# slush_cap_board_hardctrl_rev_C.net
KiCad netlist of a schematic drawn in EAGLE
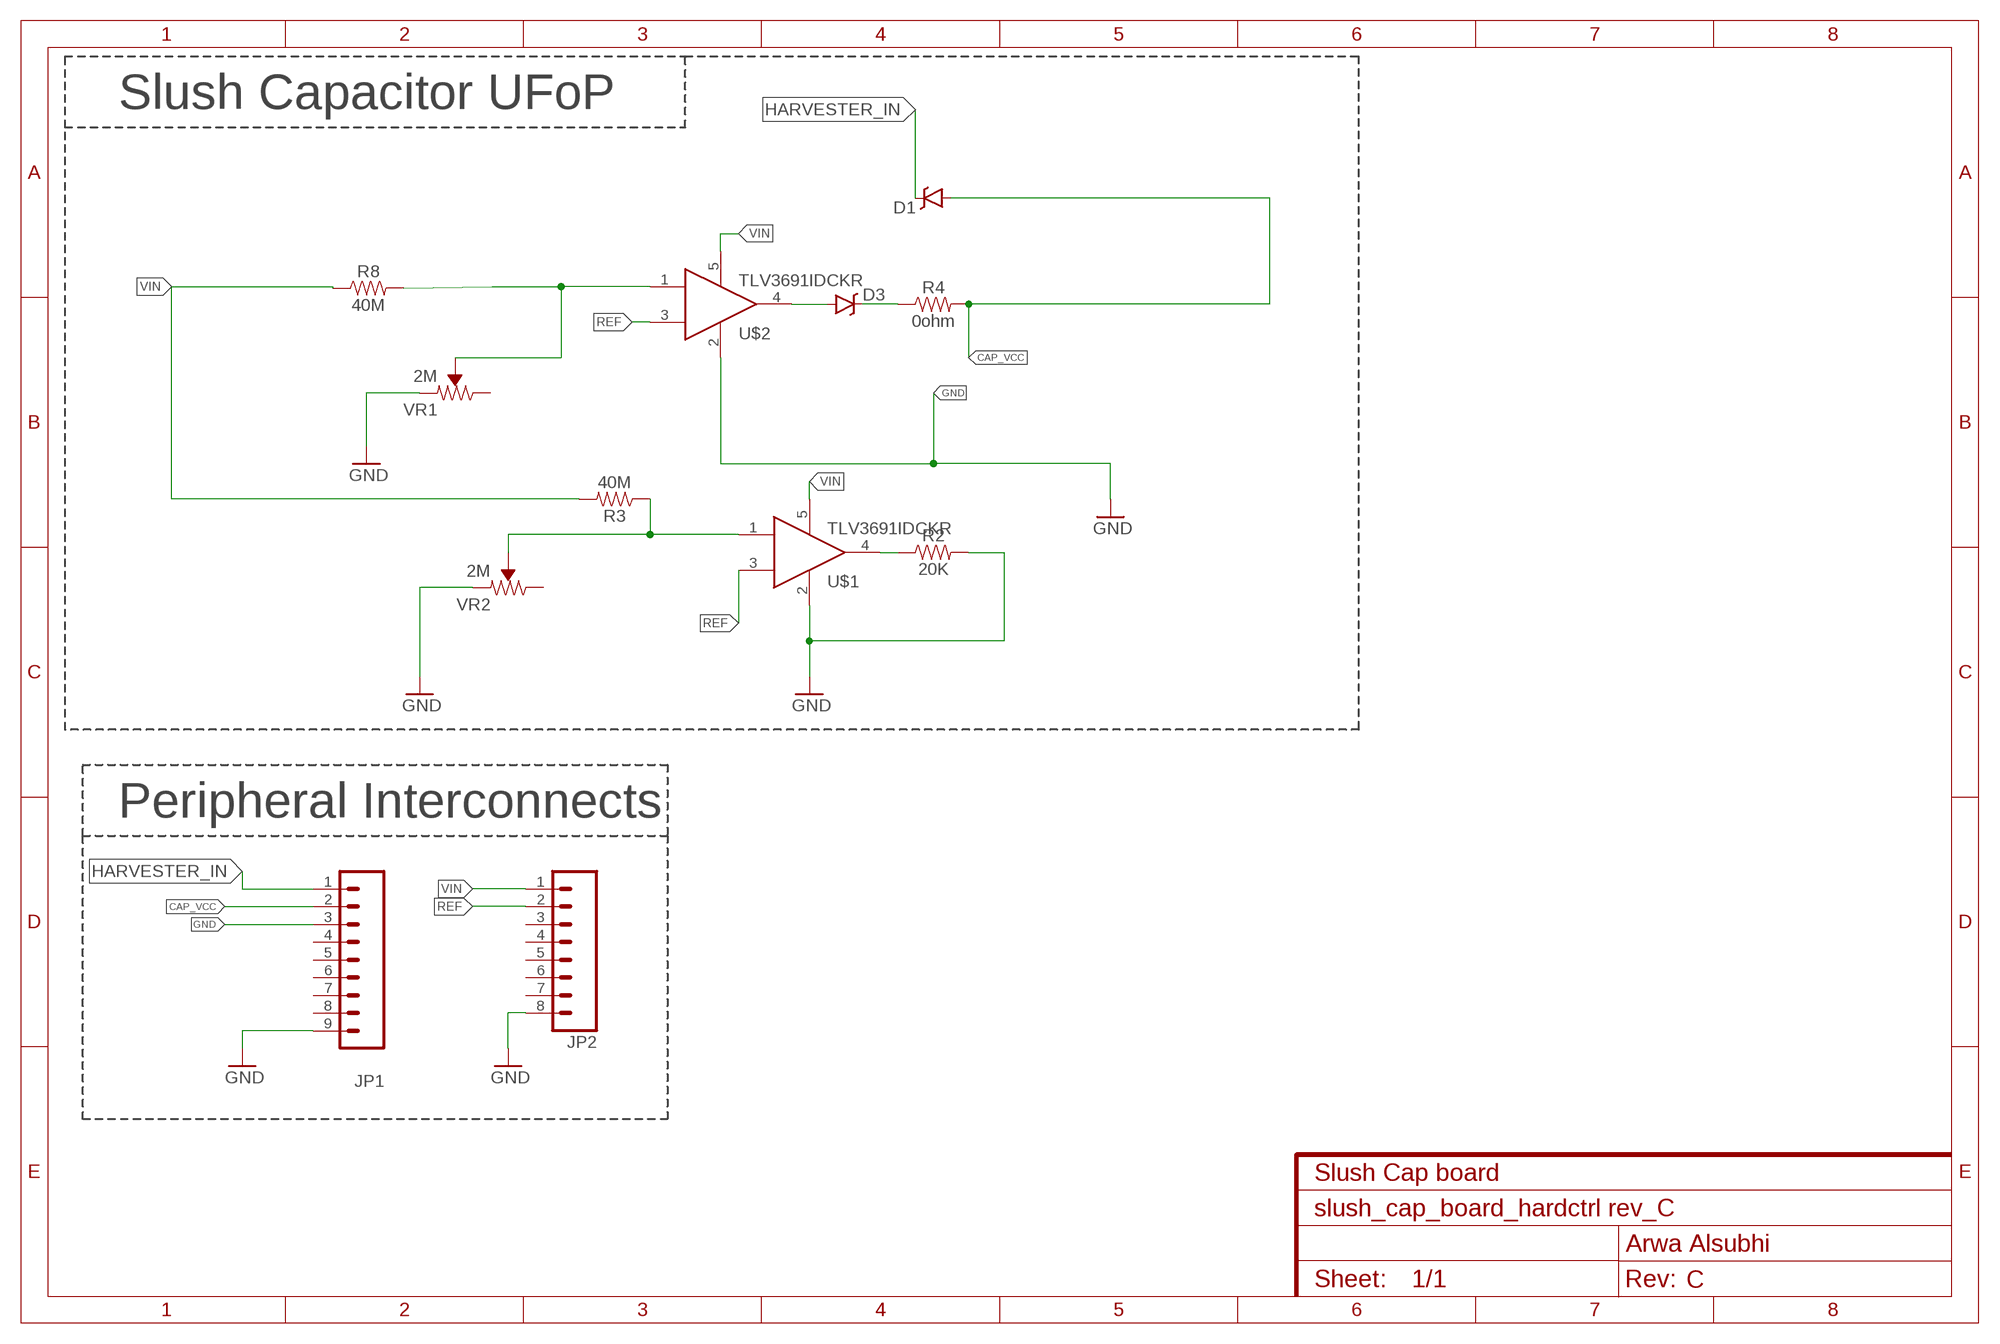
[diagram p0: schematic, sheet 1]

(export (version "E")
  (design (tool "Eeschema 10.0.6"))
  (components
    (comp (ref "D1")
      (value "RB751")
      (footprint "eagle-import:SOD-523")
      (fields (field (name "MPN") "BAS40-02V-V-G-08"))
      (libsource (lib "eagle-import") (part "DIODE-SCHOTTKY-RB751"))
    )
    (comp (ref "D3")
      (value "RB751")
      (footprint "eagle-import:SOD-523")
      (fields (field (name "MPN") "BAS40-02V-V-G-08"))
      (libsource (lib "eagle-import") (part "DIODE-SCHOTTKY-RB751"))
    )
    (comp (ref "JP1")
      (value "M091.27MM")
      (footprint "eagle-import:1X09-1.27MM")
      (fields (field (name "MANUFACTURERPARTNUMBER") "GRPB091VWVN-RC ") (field (name "MPN") "GRPB091VWVN-RC"))
      (libsource (lib "eagle-import") (part "M091.27MM"))
    )
    (comp (ref "JP2")
      (value "M081.27MM")
      (footprint "eagle-import:1X08-1.27MM")
      (fields (field (name "MANUFACTURERPARTNUMBER") "GRPB081VWVN-RC "))
      (libsource (lib "eagle-import") (part "M081.27MM"))
    )
    (comp (ref "R2")
      (value "20K")
      (footprint "eagle-import:0805")
      (libsource (lib "eagle-import") (part "0.3OHM-0805-1/8W-1%"))
    )
    (comp (ref "R3")
      (value "40M")
      (footprint "eagle-import:0805")
      (libsource (lib "eagle-import") (part "0.3OHM-0805-1/8W-1%"))
    )
    (comp (ref "R4")
      (value "0ohm")
      (footprint "eagle-import:0603")
      (libsource (lib "eagle-import") (part "0603-RESISTOR-0603-1/10W-1%"))
    )
    (comp (ref "R8")
      (value "40M")
      (footprint "eagle-import:0805")
      (libsource (lib "eagle-import") (part "0.3OHM-0805-1/8W-1%"))
    )
    (comp (ref "U$1")
      (value "TLV3691IDCKR")
      (footprint "eagle-import:SOT353")
      (libsource (lib "eagle-import") (part "TLV3691IDCKR"))
    )
    (comp (ref "U$2")
      (value "TLV3691IDCKR")
      (footprint "eagle-import:SOT353")
      (libsource (lib "eagle-import") (part "TLV3691IDCKR"))
    )
    (comp (ref "VR1")
      (value "2M")
      (footprint "eagle-import:TRIMPOT-SMD-3MM-CLOSED")
      (libsource (lib "eagle-import") (part "TRIMPOT-SMD-3MM-CLOSED-1/8W-20%"))
    )
    (comp (ref "VR2")
      (value "2M")
      (footprint "eagle-import:TRIMPOT-SMD-3MM-CLOSED")
      (libsource (lib "eagle-import") (part "TRIMPOT-SMD-3MM-CLOSED-1/8W-20%"))
    )
  )
  (nets
    (net (code "1") (name "CAP_VCC") (class "Default")
      (node (ref "D1") (pin "A") (pinfunction "A_A") (pintype "passive"))
      (node (ref "JP1") (pin "2") (pinfunction "2_2") (pintype "passive"))
      (node (ref "R4") (pin "2") (pinfunction "2_2") (pintype "passive"))
    )
    (net (code "2") (name "GND") (class "Default")
      (node (ref "JP1") (pin "3") (pinfunction "3_3") (pintype "passive"))
      (node (ref "JP1") (pin "9") (pinfunction "9_9") (pintype "passive"))
      (node (ref "JP2") (pin "8") (pinfunction "8_8") (pintype "passive"))
      (node (ref "R2") (pin "2") (pinfunction "2_2") (pintype "passive"))
      (node (ref "U$1") (pin "2") (pinfunction "2_2") (pintype "bidirectional"))
      (node (ref "U$2") (pin "2") (pinfunction "2_2") (pintype "bidirectional"))
      (node (ref "VR1") (pin "1") (pinfunction "CCW_1") (pintype "passive"))
      (node (ref "VR2") (pin "1") (pinfunction "CCW_1") (pintype "passive"))
    )
    (net (code "3") (name "HARVESTER_IN") (class "Default")
      (node (ref "D1") (pin "C") (pinfunction "C_C") (pintype "passive"))
      (node (ref "JP1") (pin "1") (pinfunction "1_1") (pintype "passive"))
    )
    (net (code "4") (name "Net-(D3-PadA)") (class "Default")
      (node (ref "D3") (pin "A") (pinfunction "A_A") (pintype "passive"))
      (node (ref "U$2") (pin "4") (pinfunction "4_4") (pintype "bidirectional"))
    )
    (net (code "5") (name "Net-(D3-PadC)") (class "Default")
      (node (ref "D3") (pin "C") (pinfunction "C_C") (pintype "passive"))
      (node (ref "R4") (pin "1") (pinfunction "1_1") (pintype "passive"))
    )
    (net (code "6") (name "Net-(R2-Pad1)") (class "Default")
      (node (ref "R2") (pin "1") (pinfunction "1_1") (pintype "passive"))
      (node (ref "U$1") (pin "4") (pinfunction "4_4") (pintype "bidirectional"))
    )
    (net (code "7") (name "Net-(VR1-WIPER)") (class "Default")
      (node (ref "R8") (pin "2") (pinfunction "2_2") (pintype "passive"))
      (node (ref "U$2") (pin "1") (pinfunction "1_1") (pintype "bidirectional"))
      (node (ref "VR1") (pin "2") (pinfunction "WIPER_2") (pintype "passive"))
    )
    (net (code "8") (name "Net-(VR2-WIPER)") (class "Default")
      (node (ref "R3") (pin "1") (pinfunction "1_1") (pintype "passive"))
      (node (ref "U$1") (pin "1") (pinfunction "1_1") (pintype "bidirectional"))
      (node (ref "VR2") (pin "2") (pinfunction "WIPER_2") (pintype "passive"))
    )
    (net (code "9") (name "REF") (class "Default")
      (node (ref "JP2") (pin "2") (pinfunction "2_2") (pintype "passive"))
      (node (ref "U$1") (pin "3") (pinfunction "3_3") (pintype "bidirectional"))
      (node (ref "U$2") (pin "3") (pinfunction "3_3") (pintype "bidirectional"))
    )
    (net (code "10") (name "VIN") (class "Default")
      (node (ref "JP2") (pin "1") (pinfunction "1_1") (pintype "passive"))
      (node (ref "R3") (pin "2") (pinfunction "2_2") (pintype "passive"))
      (node (ref "R8") (pin "1") (pinfunction "1_1") (pintype "passive"))
      (node (ref "U$1") (pin "5") (pinfunction "5_5") (pintype "bidirectional"))
      (node (ref "U$2") (pin "5") (pinfunction "5_5") (pintype "bidirectional"))
    )
    (net (code "11") (name "unconnected-(JP1-Pad4)") (class "Default")
      (node (ref "JP1") (pin "4") (pinfunction "4_4") (pintype "passive"))
    )
    (net (code "12") (name "unconnected-(JP1-Pad5)") (class "Default")
      (node (ref "JP1") (pin "5") (pinfunction "5_5") (pintype "passive"))
    )
    (net (code "13") (name "unconnected-(JP1-Pad6)") (class "Default")
      (node (ref "JP1") (pin "6") (pinfunction "6_6") (pintype "passive"))
    )
    (net (code "14") (name "unconnected-(JP1-Pad7)") (class "Default")
      (node (ref "JP1") (pin "7") (pinfunction "7_7") (pintype "passive"))
    )
    (net (code "15") (name "unconnected-(JP1-Pad8)") (class "Default")
      (node (ref "JP1") (pin "8") (pinfunction "8_8") (pintype "passive"))
    )
    (net (code "16") (name "unconnected-(JP2-Pad3)") (class "Default")
      (node (ref "JP2") (pin "3") (pinfunction "3_3") (pintype "passive"))
    )
    (net (code "17") (name "unconnected-(JP2-Pad4)") (class "Default")
      (node (ref "JP2") (pin "4") (pinfunction "4_4") (pintype "passive"))
    )
    (net (code "18") (name "unconnected-(JP2-Pad5)") (class "Default")
      (node (ref "JP2") (pin "5") (pinfunction "5_5") (pintype "passive"))
    )
    (net (code "19") (name "unconnected-(JP2-Pad6)") (class "Default")
      (node (ref "JP2") (pin "6") (pinfunction "6_6") (pintype "passive"))
    )
    (net (code "20") (name "unconnected-(JP2-Pad7)") (class "Default")
      (node (ref "JP2") (pin "7") (pinfunction "7_7") (pintype "passive"))
    )
    (net (code "21") (name "unconnected-(VR1-CW-Pad3)") (class "Default")
      (node (ref "VR1") (pin "3") (pinfunction "CW_3") (pintype "passive"))
    )
    (net (code "22") (name "unconnected-(VR2-CW-Pad3)") (class "Default")
      (node (ref "VR2") (pin "3") (pinfunction "CW_3") (pintype "passive"))
    )
  )
)
